# ADC.net
KiCad netlist of a schematic drawn in Altium Designer
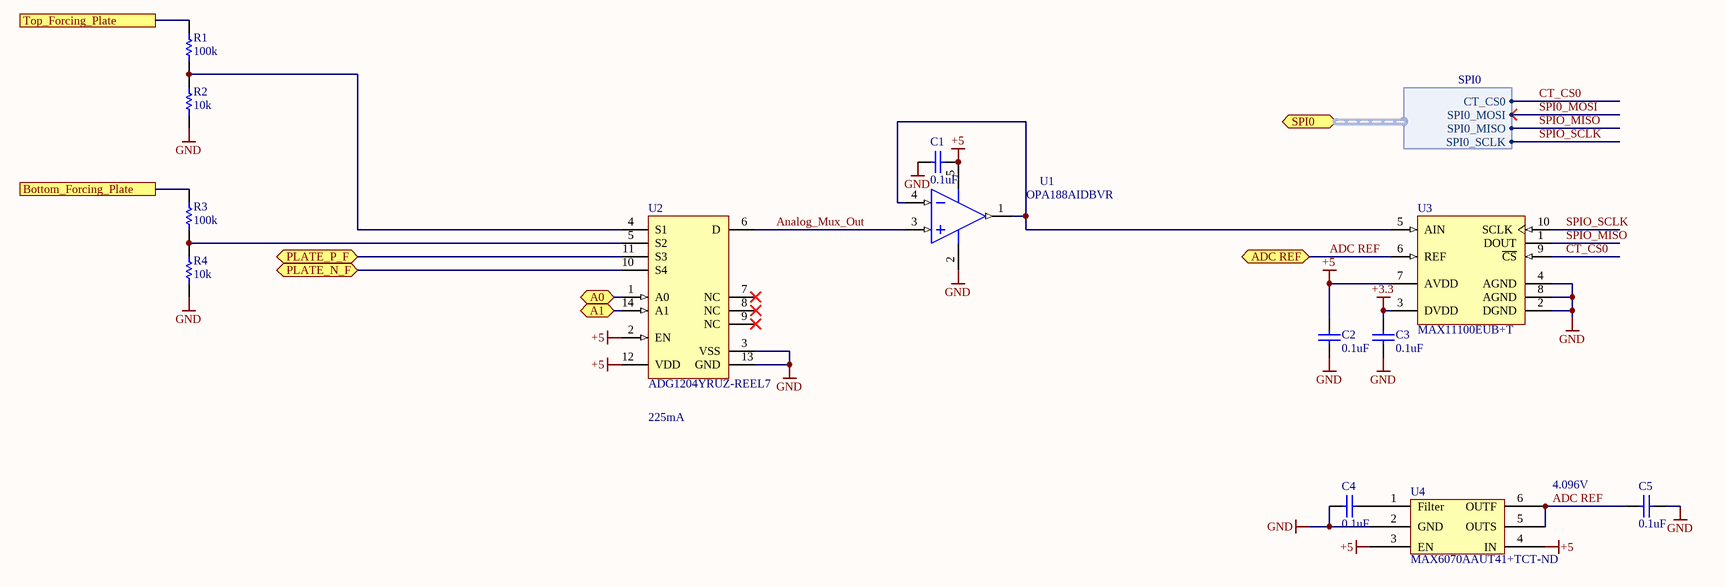
[diagram p0: ADC.SchDoc]

(export (version "E")
  (design (tool "Eeschema 10.0.6"))
  (components
    (comp (ref "C1")
      (value "0.1uF")
      (footprint "CAPC0402(1005)60_L")
      (description "CAP CER 0.1UF 10V X7R 0402")
      (fields
        (field (name "MANUFACTURER") "Murata Electronics North America")
        (field (name "MANUFACTURER PART NUMBER") "GRM155R71A104KA01D")
      )
      (libsource (lib "Altium Content Vault") (part "CMP-1034-00252-1"))
    )
    (comp (ref "C2")
      (value "0.1uF")
      (footprint "CAPC0402(1005)60_L")
      (description "CAP CER 0.1UF 10V X7R 0402")
      (fields
        (field (name "MANUFACTURER") "Murata Electronics North America")
        (field (name "MANUFACTURER PART NUMBER") "GRM155R71A104KA01D")
      )
      (libsource (lib "Altium Content Vault") (part "CMP-1034-00252-1"))
    )
    (comp (ref "C3")
      (value "0.1uF")
      (footprint "CAPC0402(1005)60_L")
      (description "CAP CER 0.1UF 10V X7R 0402")
      (fields
        (field (name "MANUFACTURER") "Murata Electronics North America")
        (field (name "MANUFACTURER PART NUMBER") "GRM155R71A104KA01D")
      )
      (libsource (lib "Altium Content Vault") (part "CMP-1034-00252-1"))
    )
    (comp (ref "C4")
      (value "0.1uF")
      (footprint "CAPC0402(1005)60_L")
      (description "CAP CER 0.1UF 10V X7R 0402")
      (fields
        (field (name "MANUFACTURER") "Murata Electronics North America")
        (field (name "MANUFACTURER PART NUMBER") "GRM155R71A104KA01D")
      )
      (libsource (lib "Altium Content Vault") (part "CMP-1034-00252-1"))
    )
    (comp (ref "C5")
      (value "0.1uF")
      (footprint "CAPC0402(1005)60_L")
      (description "CAP CER 0.1UF 10V X7R 0402")
      (fields
        (field (name "MANUFACTURER") "Murata Electronics North America")
        (field (name "MANUFACTURER PART NUMBER") "GRM155R71A104KA01D")
      )
      (libsource (lib "Altium Content Vault") (part "CMP-1034-00252-1"))
    )
    (comp (ref "R1")
      (value "100k")
      (footprint "RESC0402(1005)_M")
      (libsource (lib "Altium Content Vault") (part "CMP-1011-00463-1"))
    )
    (comp (ref "R2")
      (value "10k")
      (footprint "RESC0402(1005)_M")
      (libsource (lib "Altium Content Vault") (part "CMP-1011-00463-1"))
    )
    (comp (ref "R3")
      (value "100k")
      (footprint "RESC0402(1005)_M")
      (libsource (lib "Altium Content Vault") (part "CMP-1011-00463-1"))
    )
    (comp (ref "R4")
      (value "10k")
      (footprint "RESC0402(1005)_M")
      (libsource (lib "Altium Content Vault") (part "CMP-1011-00463-1"))
    )
    (comp (ref "U1")
      (value "OPA188AIDBVR")
      (footprint "DBV0005A_M")
      (fields (field (name "MANUFACTURER") "Texas Instruments"))
      (libsource (lib "Altium Content Vault") (part "CMP-0809-00005-2"))
    )
    (comp (ref "U2")
      (value "ADG1204YRUZ-REEL7")
      (footprint "ADI-RU-14_L")
      (fields
        (field (name "MANUFACTURER") "Maxim Integrated")
        (field (name "MANUFACTURER PART NUMBER") "MAX11100EUB+")
        (field (name "BASE PART NUMBER") "MAX11100")
      )
      (libsource (lib "Altium Content Vault") (part "CMP-0793-00109-1"))
    )
    (comp (ref "U3")
      (value "MAX11100EUB+T")
      (footprint "U10+2_L")
      (description "16-Bit, +5V, 200ksps ADC with 10uA Shutdown, 10-Pin uMAX, -40°C to +85°C, Pb-Free, Tape and Reel")
      (fields
        (field (name "MANUFACTURER") "Maxim Integrated")
        (field (name "MANUFACTURER PART NUMBER") "MAX11100EUB+")
      )
      (libsource (lib "Altium Content Vault") (part "CMP-0249-00017-1"))
    )
    (comp (ref "U4")
      (value "MAX6070AAUT41+T")
      (footprint "SOT95P280X445-6N")
      (description "IC VREF SERIES 4.096V SOT23")
      (fields
        (field (name "SUPPLIER PART NUMBER 1") "MAX6070AAUT41+TCT-ND")
        (field (name "MANUFACTURER") "Maxim Integrated")
        (field (name "TOLERANCE") "±0.04%")
      )
      (libsource (lib "ZLS_Schematic_lib") (part "MAX6070AAUT41+T"))
    )
  )
  (nets
    (net (code "2") (name "+3.3") (class "Default")
      (node (ref "C3") (pin "2") (pinfunction "2_2") (pintype "passive"))
      (node (ref "U3") (pin "3") (pinfunction "DVDD_3") (pintype "power_in"))
    )
    (net (code "3") (name "+5") (class "Default")
      (node (ref "C1") (pin "2") (pinfunction "2_2") (pintype "passive"))
      (node (ref "C2") (pin "2") (pinfunction "2_2") (pintype "passive"))
      (node (ref "U1") (pin "5") (pinfunction "V+_5") (pintype "power_in"))
      (node (ref "U2") (pin "12") (pinfunction "VDD_12") (pintype "power_in"))
      (node (ref "U2") (pin "2") (pinfunction "EN_2") (pintype "input"))
      (node (ref "U3") (pin "7") (pinfunction "AVDD_7") (pintype "power_in"))
      (node (ref "U4") (pin "3") (pinfunction "EN_3") (pintype "passive"))
      (node (ref "U4") (pin "4") (pinfunction "IN_4") (pintype "passive"))
    )
    (net (code "4") (name "/A0") (class "Default")
      (node (ref "U2") (pin "1") (pinfunction "A0_1") (pintype "input"))
    )
    (net (code "5") (name "/A1") (class "Default")
      (node (ref "U2") (pin "14") (pinfunction "A1_14") (pintype "input"))
    )
    (net (code "6") (name "/ADC REF") (class "Default")
      (node (ref "C5") (pin "1") (pinfunction "1_1") (pintype "passive"))
      (node (ref "U3") (pin "6") (pinfunction "REF_6") (pintype "input"))
      (node (ref "U4") (pin "5") (pinfunction "OUTS_5") (pintype "passive"))
      (node (ref "U4") (pin "6") (pinfunction "OUTF_6") (pintype "passive"))
    )
    (net (code "7") (name "/Analog_Mux_Out") (class "Default")
      (node (ref "U1") (pin "3") (pinfunction "IN+_3") (pintype "input"))
      (node (ref "U2") (pin "6") (pinfunction "D_6") (pintype "passive"))
    )
    (net (code "8") (name "/Bottom_Forcing_Plate") (class "Default")
      (node (ref "R3") (pin "1") (pinfunction "1_1") (pintype "passive"))
    )
    (net (code "9") (name "/CT_CS0") (class "Default")
      (node (ref "U3") (pin "9") (pinfunction "~{CS}_9") (pintype "input"))
    )
    (net (code "10") (name "/PLATE_N_F") (class "Default")
      (node (ref "U2") (pin "10") (pinfunction "S4_10") (pintype "passive"))
    )
    (net (code "11") (name "/PLATE_P_F") (class "Default")
      (node (ref "U2") (pin "11") (pinfunction "S3_11") (pintype "passive"))
    )
    (net (code "13") (name "/SPIO_MISO") (class "Default")
      (node (ref "U3") (pin "1") (pinfunction "DOUT_1") (pintype "tri_state"))
    )
    (net (code "14") (name "/SPIO_SCLK") (class "Default")
      (node (ref "U3") (pin "10") (pinfunction "SCLK_10") (pintype "input"))
    )
    (net (code "15") (name "/Top_Forcing_Plate") (class "Default")
      (node (ref "R1") (pin "1") (pinfunction "1_1") (pintype "passive"))
    )
    (net (code "17") (name "GND") (class "Default")
      (node (ref "C1") (pin "1") (pinfunction "1_1") (pintype "passive"))
      (node (ref "C2") (pin "1") (pinfunction "1_1") (pintype "passive"))
      (node (ref "C3") (pin "1") (pinfunction "1_1") (pintype "passive"))
      (node (ref "C4") (pin "1") (pinfunction "1_1") (pintype "passive"))
      (node (ref "C5") (pin "2") (pinfunction "2_2") (pintype "passive"))
      (node (ref "R2") (pin "2") (pinfunction "2_2") (pintype "passive"))
      (node (ref "R4") (pin "2") (pinfunction "2_2") (pintype "passive"))
      (node (ref "U1") (pin "2") (pinfunction "V-_2") (pintype "power_in"))
      (node (ref "U2") (pin "13") (pinfunction "GND_13") (pintype "power_in"))
      (node (ref "U2") (pin "3") (pinfunction "VSS_3") (pintype "power_in"))
      (node (ref "U3") (pin "2") (pinfunction "DGND_2") (pintype "power_in"))
      (node (ref "U3") (pin "4") (pinfunction "AGND_4") (pintype "power_in"))
      (node (ref "U3") (pin "8") (pinfunction "AGND_8") (pintype "power_in"))
      (node (ref "U4") (pin "2") (pinfunction "GND_2") (pintype "passive"))
    )
    (net (code "18") (name "Net-(U1-IN-)") (class "Default")
      (node (ref "U1") (pin "1") (pinfunction "OUT_1") (pintype "output"))
      (node (ref "U1") (pin "4") (pinfunction "IN-_4") (pintype "input"))
      (node (ref "U3") (pin "5") (pinfunction "AIN_5") (pintype "input"))
    )
    (net (code "19") (name "Net-(U2-S1)") (class "Default")
      (node (ref "R1") (pin "2") (pinfunction "2_2") (pintype "passive"))
      (node (ref "R2") (pin "1") (pinfunction "1_1") (pintype "passive"))
      (node (ref "U2") (pin "4") (pinfunction "S1_4") (pintype "passive"))
    )
    (net (code "20") (name "Net-(U2-S2)") (class "Default")
      (node (ref "R3") (pin "2") (pinfunction "2_2") (pintype "passive"))
      (node (ref "R4") (pin "1") (pinfunction "1_1") (pintype "passive"))
      (node (ref "U2") (pin "5") (pinfunction "S2_5") (pintype "passive"))
    )
    (net (code "21") (name "Net-(U4-Filter)") (class "Default")
      (node (ref "C4") (pin "2") (pinfunction "2_2") (pintype "passive"))
      (node (ref "U4") (pin "1") (pinfunction "Filter_1") (pintype "passive"))
    )
    (net (code "22") (name "unconnected-(U2-NC-Pad7)") (class "Default")
      (node (ref "U2") (pin "7") (pinfunction "NC_7") (pintype "passive+no_connect"))
    )
    (net (code "23") (name "unconnected-(U2-NC-Pad8)") (class "Default")
      (node (ref "U2") (pin "8") (pinfunction "NC_8") (pintype "passive+no_connect"))
    )
    (net (code "24") (name "unconnected-(U2-NC-Pad9)") (class "Default")
      (node (ref "U2") (pin "9") (pinfunction "NC_9") (pintype "passive+no_connect"))
    )
  )
)
